# ACS_Board_Schematic.net
KiCad netlist of a schematic drawn in Altium Designer
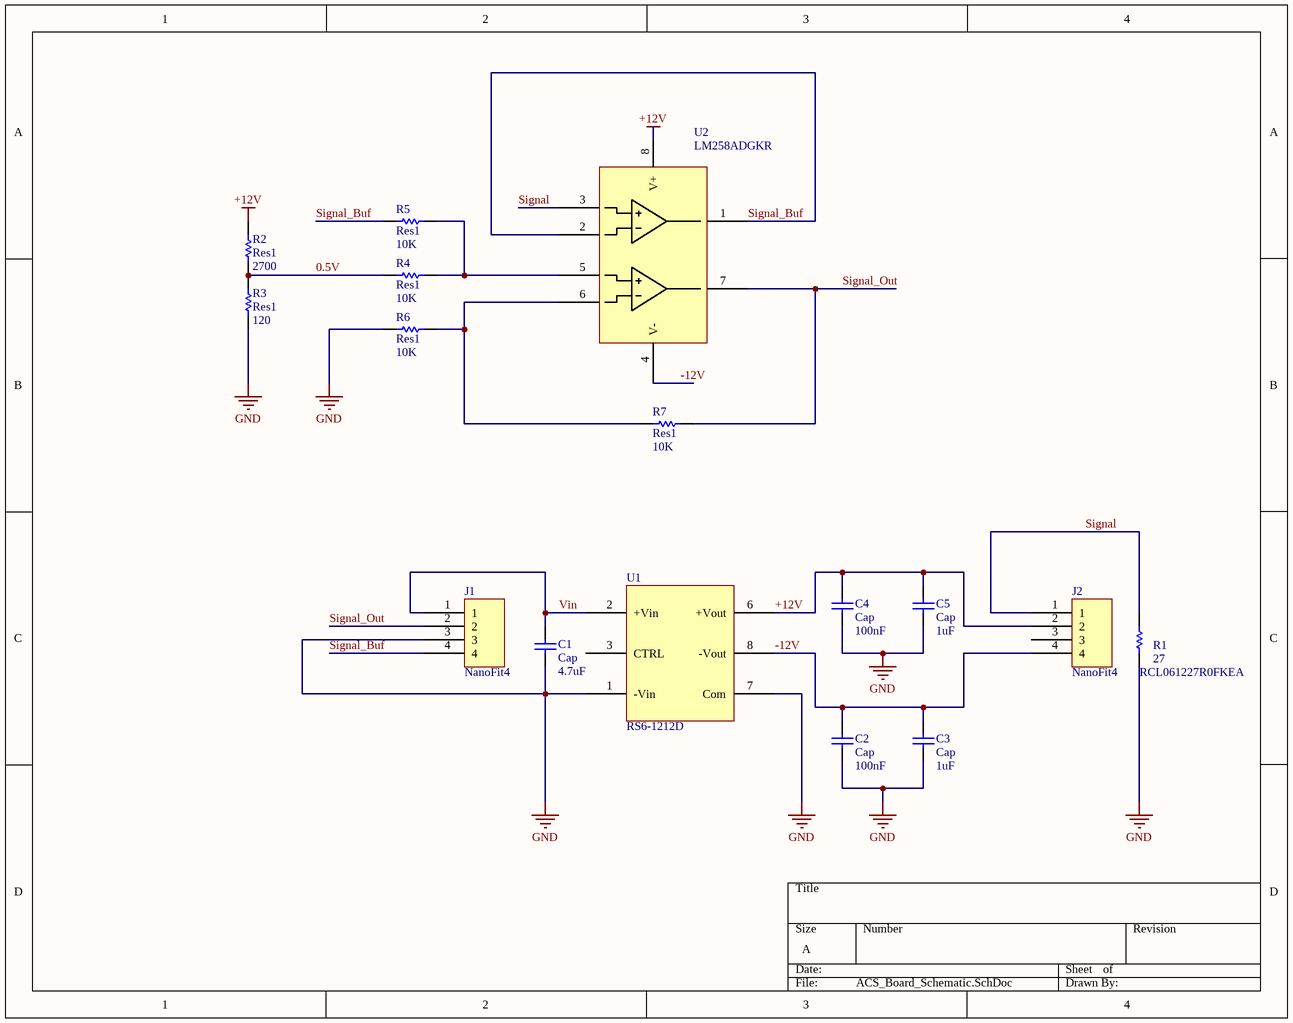
[diagram p0: ACS_Board_Schematic.SchDoc]

(export (version "E")
  (design (tool "Eeschema 10.0.6"))
  (components
    (comp (ref "C1")
      (value "Cap")
      (footprint "CAPC2012X12N")
      (description "Capacitor")
      (fields (field (name "ALTIUM_VALUE") "4.7uF") (field (name "PUBLISHER") "Altium Limited"))
      (libsource (lib "Miscellaneous Devices") (part "Cap"))
    )
    (comp (ref "C2")
      (value "Cap")
      (footprint "CAPC1608X08N")
      (description "Capacitor")
      (fields (field (name "ALTIUM_VALUE") "100nF") (field (name "PUBLISHER") "Altium Limited"))
      (libsource (lib "Miscellaneous Devices") (part "Cap"))
    )
    (comp (ref "C3")
      (value "Cap")
      (footprint "CAPC1608X08N")
      (description "Capacitor")
      (fields (field (name "ALTIUM_VALUE") "1uF") (field (name "PUBLISHER") "Altium Limited"))
      (libsource (lib "Miscellaneous Devices") (part "Cap"))
    )
    (comp (ref "C4")
      (value "Cap")
      (footprint "CAPC1608X08N")
      (description "Capacitor")
      (fields (field (name "ALTIUM_VALUE") "100nF") (field (name "PUBLISHER") "Altium Limited"))
      (libsource (lib "Miscellaneous Devices") (part "Cap"))
    )
    (comp (ref "C5")
      (value "Cap")
      (footprint "CAPC1608X08N")
      (description "Capacitor")
      (fields (field (name "ALTIUM_VALUE") "1uF") (field (name "PUBLISHER") "Altium Limited"))
      (libsource (lib "Miscellaneous Devices") (part "Cap"))
    )
    (comp (ref "J1")
      (value "NanoFit4")
      (footprint "ACS_Board_Footprints:1053141304")
      (libsource (lib "ACS_Board_Components") (part "NanoFit4"))
    )
    (comp (ref "J2")
      (value "NanoFit4")
      (footprint "ACS_Board_Footprints:1053141304")
      (libsource (lib "ACS_Board_Components") (part "NanoFit4"))
    )
    (comp (ref "R1")
      (value "RCL061227R0FKEA")
      (footprint "RCL061227R0FKEA")
      (description "Resistor")
      (fields (field (name "ALTIUM_UNNAMED_1") "27") (field (name "PUBLISHER") "Altium Limited"))
      (libsource (lib "Miscellaneous Devices") (part "Res1"))
    )
    (comp (ref "R2")
      (value "Res1")
      (footprint "RESC1608X06N")
      (description "Resistor")
      (fields (field (name "ALTIUM_VALUE") "2700") (field (name "PUBLISHER") "Altium Limited"))
      (libsource (lib "Miscellaneous Devices") (part "Res1"))
    )
    (comp (ref "R3")
      (value "Res1")
      (footprint "RESC1608X06N")
      (description "Resistor")
      (fields (field (name "ALTIUM_VALUE") "120") (field (name "PUBLISHER") "Altium Limited"))
      (libsource (lib "Miscellaneous Devices") (part "Res1"))
    )
    (comp (ref "R4")
      (value "Res1")
      (footprint "RESC1608X06N")
      (description "Resistor")
      (fields (field (name "ALTIUM_VALUE") "10K") (field (name "PUBLISHER") "Altium Limited"))
      (libsource (lib "Miscellaneous Devices") (part "Res1"))
    )
    (comp (ref "R5")
      (value "Res1")
      (footprint "RESC1608X06N")
      (description "Resistor")
      (fields (field (name "ALTIUM_VALUE") "10K") (field (name "PUBLISHER") "Altium Limited"))
      (libsource (lib "Miscellaneous Devices") (part "Res1"))
    )
    (comp (ref "R6")
      (value "Res1")
      (footprint "RESC1608X06N")
      (description "Resistor")
      (fields (field (name "ALTIUM_VALUE") "10K") (field (name "PUBLISHER") "Altium Limited"))
      (libsource (lib "Miscellaneous Devices") (part "Res1"))
    )
    (comp (ref "R7")
      (value "Res1")
      (footprint "RESC1608X06N")
      (description "Resistor")
      (fields (field (name "ALTIUM_VALUE") "10K") (field (name "PUBLISHER") "Altium Limited"))
      (libsource (lib "Miscellaneous Devices") (part "Res1"))
    )
    (comp (ref "U1")
      (value "RS6-1212D")
      (footprint "RS6-1212D")
      (libsource (lib "ACS_Board_Components") (part "RS6-1212D"))
    )
    (comp (ref "U2")
      (value "LM258ADGKR")
      (footprint "TSOP65P640X120-8N")
      (libsource (lib "ACS_Board_Components") (part "OPAMP2"))
    )
  )
  (nets
    (net (code "1") (name "+12V") (class "Default")
      (node (ref "C4") (pin "2") (pinfunction "2_2") (pintype "passive"))
      (node (ref "C5") (pin "2") (pinfunction "2_2") (pintype "passive"))
      (node (ref "J2") (pin "2") (pinfunction "2_2") (pintype "passive"))
      (node (ref "R2") (pin "2") (pinfunction "2_2") (pintype "passive"))
      (node (ref "U1") (pin "6") (pinfunction "+Vout_6") (pintype "passive"))
      (node (ref "U2") (pin "8") (pinfunction "V+_8") (pintype "passive"))
    )
    (net (code "2") (name "/-12V") (class "Default")
      (node (ref "C2") (pin "2") (pinfunction "2_2") (pintype "passive"))
      (node (ref "C3") (pin "2") (pinfunction "2_2") (pintype "passive"))
      (node (ref "J2") (pin "4") (pinfunction "4_4") (pintype "passive"))
      (node (ref "U1") (pin "8") (pinfunction "-Vout_8") (pintype "passive"))
      (node (ref "U2") (pin "4") (pinfunction "V-_4") (pintype "passive"))
    )
    (net (code "3") (name "/0.5V") (class "Default")
      (node (ref "R2") (pin "1") (pinfunction "1_1") (pintype "passive"))
      (node (ref "R3") (pin "2") (pinfunction "2_2") (pintype "passive"))
      (node (ref "R4") (pin "1") (pinfunction "1_1") (pintype "passive"))
    )
    (net (code "4") (name "/Signal") (class "Default")
      (node (ref "J2") (pin "1") (pinfunction "1_1") (pintype "passive"))
      (node (ref "R1") (pin "2") (pinfunction "2_2") (pintype "passive"))
      (node (ref "U2") (pin "3") (pinfunction "IN1+_3") (pintype "passive"))
    )
    (net (code "5") (name "/Signal_Buf") (class "Default")
      (node (ref "J1") (pin "4") (pinfunction "4_4") (pintype "passive"))
      (node (ref "R5") (pin "1") (pinfunction "1_1") (pintype "passive"))
      (node (ref "U2") (pin "1") (pinfunction "OUT1_1") (pintype "passive"))
      (node (ref "U2") (pin "2") (pinfunction "IN1-_2") (pintype "passive"))
    )
    (net (code "6") (name "/Signal_Out") (class "Default")
      (node (ref "J1") (pin "2") (pinfunction "2_2") (pintype "passive"))
      (node (ref "R7") (pin "2") (pinfunction "2_2") (pintype "passive"))
      (node (ref "U2") (pin "7") (pinfunction "OUT2_7") (pintype "passive"))
    )
    (net (code "7") (name "/Vin") (class "Default")
      (node (ref "C1") (pin "2") (pinfunction "2_2") (pintype "passive"))
      (node (ref "J1") (pin "1") (pinfunction "1_1") (pintype "passive"))
      (node (ref "U1") (pin "2") (pinfunction "+Vin_2") (pintype "passive"))
    )
    (net (code "8") (name "GND") (class "Default")
      (node (ref "C1") (pin "1") (pinfunction "1_1") (pintype "passive"))
      (node (ref "C2") (pin "1") (pinfunction "1_1") (pintype "passive"))
      (node (ref "C3") (pin "1") (pinfunction "1_1") (pintype "passive"))
      (node (ref "C4") (pin "1") (pinfunction "1_1") (pintype "passive"))
      (node (ref "C5") (pin "1") (pinfunction "1_1") (pintype "passive"))
      (node (ref "J1") (pin "3") (pinfunction "3_3") (pintype "passive"))
      (node (ref "R1") (pin "1") (pinfunction "1_1") (pintype "passive"))
      (node (ref "R3") (pin "1") (pinfunction "1_1") (pintype "passive"))
      (node (ref "R6") (pin "1") (pinfunction "1_1") (pintype "passive"))
      (node (ref "U1") (pin "1") (pinfunction "-Vin_1") (pintype "passive"))
      (node (ref "U1") (pin "7") (pinfunction "Com_7") (pintype "passive"))
    )
    (net (code "9") (name "Net-(U2-IN2+)") (class "Default")
      (node (ref "R4") (pin "2") (pinfunction "2_2") (pintype "passive"))
      (node (ref "R5") (pin "2") (pinfunction "2_2") (pintype "passive"))
      (node (ref "U2") (pin "5") (pinfunction "IN2+_5") (pintype "passive"))
    )
    (net (code "10") (name "Net-(U2-IN2-)") (class "Default")
      (node (ref "R6") (pin "2") (pinfunction "2_2") (pintype "passive"))
      (node (ref "R7") (pin "1") (pinfunction "1_1") (pintype "passive"))
      (node (ref "U2") (pin "6") (pinfunction "IN2-_6") (pintype "passive"))
    )
    (net (code "11") (name "unconnected-(J2-Pad3)") (class "Default")
      (node (ref "J2") (pin "3") (pinfunction "3_3") (pintype "passive"))
    )
    (net (code "12") (name "unconnected-(U1-CTRL-Pad3)") (class "Default")
      (node (ref "U1") (pin "3") (pinfunction "CTRL_3") (pintype "passive"))
    )
  )
)
